# LDO_LM_POWER_two_78.net
KiCad netlist of a schematic drawn in Altium Designer
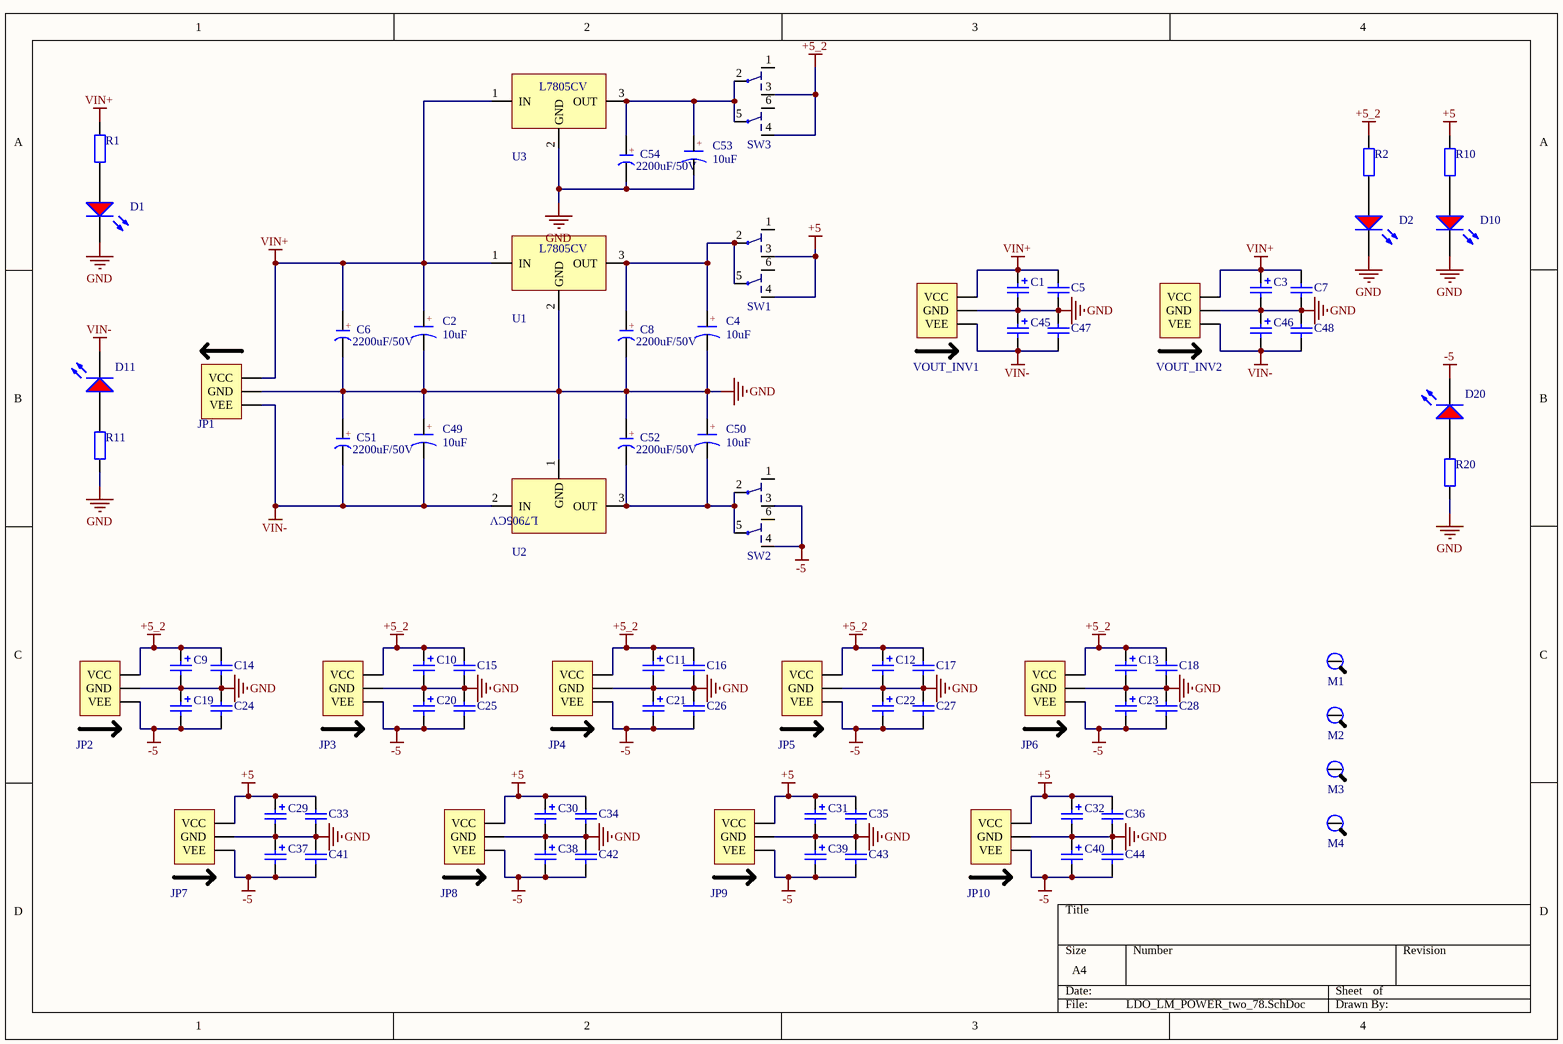
[diagram p0: LDO_LM_POWER_two_78.SchDoc]

(export (version "E")
  (design (tool "Eeschema 10.0.6"))
  (components
    (comp (ref "C1")
      (value "10uF (106) ±10% 16V")
      (footprint "CASE-A_3216")
      (description "钽电容")
      (libsource (lib "JLC") (part "3216 10uF (106) 10% 16V"))
    )
    (comp (ref "C2")
      (value "10uF")
      (footprint "226C")
      (description "贴片钽电容")
      (fields (field (name "Comment") "CAP+"))
      (libsource (lib "Cooperation") (part "0CAP+"))
    )
    (comp (ref "C3")
      (value "10uF (106) ±10% 16V")
      (footprint "CASE-A_3216")
      (description "钽电容")
      (libsource (lib "JLC") (part "3216 10uF (106) 10% 16V"))
    )
    (comp (ref "C4")
      (value "10uF")
      (footprint "226C")
      (description "贴片钽电容")
      (fields (field (name "Comment") "CAP+"))
      (libsource (lib "Cooperation") (part "0CAP+"))
    )
    (comp (ref "C5")
      (value "100nF (104) 10% 50V")
      (footprint "0603_C")
      (description "贴片电容")
      (libsource (lib "JLC") (part "0603 100nF (104) 10% 50V"))
    )
    (comp (ref "C6")
      (value "2200uF/50V")
      (footprint "2200uF/50V")
      (description "直插电解电容")
      (libsource (lib "Cooperation") (part "CAP_2200uF/50V"))
    )
    (comp (ref "C7")
      (value "100nF (104) 10% 50V")
      (footprint "0603_C")
      (description "贴片电容")
      (libsource (lib "JLC") (part "0603 100nF (104) 10% 50V"))
    )
    (comp (ref "C8")
      (value "2200uF/50V")
      (footprint "2200uF/50V")
      (description "直插电解电容")
      (libsource (lib "Cooperation") (part "CAP_2200uF/50V"))
    )
    (comp (ref "C9")
      (value "10uF (106) ±10% 16V")
      (footprint "CASE-A_3216")
      (description "钽电容")
      (libsource (lib "JLC") (part "3216 10uF (106) 10% 16V"))
    )
    (comp (ref "C10")
      (value "10uF (106) ±10% 16V")
      (footprint "CASE-A_3216")
      (description "钽电容")
      (libsource (lib "JLC") (part "3216 10uF (106) 10% 16V"))
    )
    (comp (ref "C11")
      (value "10uF (106) ±10% 16V")
      (footprint "CASE-A_3216")
      (description "钽电容")
      (libsource (lib "JLC") (part "3216 10uF (106) 10% 16V"))
    )
    (comp (ref "C12")
      (value "10uF (106) ±10% 16V")
      (footprint "CASE-A_3216")
      (description "钽电容")
      (libsource (lib "JLC") (part "3216 10uF (106) 10% 16V"))
    )
    (comp (ref "C13")
      (value "10uF (106) ±10% 16V")
      (footprint "CASE-A_3216")
      (description "钽电容")
      (libsource (lib "JLC") (part "3216 10uF (106) 10% 16V"))
    )
    (comp (ref "C14")
      (value "100nF (104) 10% 50V")
      (footprint "0603_C")
      (description "贴片电容")
      (libsource (lib "JLC") (part "0603 100nF (104) 10% 50V"))
    )
    (comp (ref "C15")
      (value "100nF (104) 10% 50V")
      (footprint "0603_C")
      (description "贴片电容")
      (libsource (lib "JLC") (part "0603 100nF (104) 10% 50V"))
    )
    (comp (ref "C16")
      (value "100nF (104) 10% 50V")
      (footprint "0603_C")
      (description "贴片电容")
      (libsource (lib "JLC") (part "0603 100nF (104) 10% 50V"))
    )
    (comp (ref "C17")
      (value "100nF (104) 10% 50V")
      (footprint "0603_C")
      (description "贴片电容")
      (libsource (lib "JLC") (part "0603 100nF (104) 10% 50V"))
    )
    (comp (ref "C18")
      (value "100nF (104) 10% 50V")
      (footprint "0603_C")
      (description "贴片电容")
      (libsource (lib "JLC") (part "0603 100nF (104) 10% 50V"))
    )
    (comp (ref "C19")
      (value "10uF (106) ±10% 16V")
      (footprint "CASE-A_3216")
      (description "钽电容")
      (libsource (lib "JLC") (part "3216 10uF (106) 10% 16V"))
    )
    (comp (ref "C20")
      (value "10uF (106) ±10% 16V")
      (footprint "CASE-A_3216")
      (description "钽电容")
      (libsource (lib "JLC") (part "3216 10uF (106) 10% 16V"))
    )
    (comp (ref "C21")
      (value "10uF (106) ±10% 16V")
      (footprint "CASE-A_3216")
      (description "钽电容")
      (libsource (lib "JLC") (part "3216 10uF (106) 10% 16V"))
    )
    (comp (ref "C22")
      (value "10uF (106) ±10% 16V")
      (footprint "CASE-A_3216")
      (description "钽电容")
      (libsource (lib "JLC") (part "3216 10uF (106) 10% 16V"))
    )
    (comp (ref "C23")
      (value "10uF (106) ±10% 16V")
      (footprint "CASE-A_3216")
      (description "钽电容")
      (libsource (lib "JLC") (part "3216 10uF (106) 10% 16V"))
    )
    (comp (ref "C24")
      (value "100nF (104) 10% 50V")
      (footprint "0603_C")
      (description "贴片电容")
      (libsource (lib "JLC") (part "0603 100nF (104) 10% 50V"))
    )
    (comp (ref "C25")
      (value "100nF (104) 10% 50V")
      (footprint "0603_C")
      (description "贴片电容")
      (libsource (lib "JLC") (part "0603 100nF (104) 10% 50V"))
    )
    (comp (ref "C26")
      (value "100nF (104) 10% 50V")
      (footprint "0603_C")
      (description "贴片电容")
      (libsource (lib "JLC") (part "0603 100nF (104) 10% 50V"))
    )
    (comp (ref "C27")
      (value "100nF (104) 10% 50V")
      (footprint "0603_C")
      (description "贴片电容")
      (libsource (lib "JLC") (part "0603 100nF (104) 10% 50V"))
    )
    (comp (ref "C28")
      (value "100nF (104) 10% 50V")
      (footprint "0603_C")
      (description "贴片电容")
      (libsource (lib "JLC") (part "0603 100nF (104) 10% 50V"))
    )
    (comp (ref "C29")
      (value "10uF (106) ±10% 16V")
      (footprint "CASE-A_3216")
      (description "钽电容")
      (libsource (lib "JLC") (part "3216 10uF (106) 10% 16V"))
    )
    (comp (ref "C30")
      (value "10uF (106) ±10% 16V")
      (footprint "CASE-A_3216")
      (description "钽电容")
      (libsource (lib "JLC") (part "3216 10uF (106) 10% 16V"))
    )
    (comp (ref "C31")
      (value "10uF (106) ±10% 16V")
      (footprint "CASE-A_3216")
      (description "钽电容")
      (libsource (lib "JLC") (part "3216 10uF (106) 10% 16V"))
    )
    (comp (ref "C32")
      (value "10uF (106) ±10% 16V")
      (footprint "CASE-A_3216")
      (description "钽电容")
      (libsource (lib "JLC") (part "3216 10uF (106) 10% 16V"))
    )
    (comp (ref "C33")
      (value "100nF (104) 10% 50V")
      (footprint "0603_C")
      (description "贴片电容")
      (libsource (lib "JLC") (part "0603 100nF (104) 10% 50V"))
    )
    (comp (ref "C34")
      (value "100nF (104) 10% 50V")
      (footprint "0603_C")
      (description "贴片电容")
      (libsource (lib "JLC") (part "0603 100nF (104) 10% 50V"))
    )
    (comp (ref "C35")
      (value "100nF (104) 10% 50V")
      (footprint "0603_C")
      (description "贴片电容")
      (libsource (lib "JLC") (part "0603 100nF (104) 10% 50V"))
    )
    (comp (ref "C36")
      (value "100nF (104) 10% 50V")
      (footprint "0603_C")
      (description "贴片电容")
      (libsource (lib "JLC") (part "0603 100nF (104) 10% 50V"))
    )
    (comp (ref "C37")
      (value "10uF (106) ±10% 16V")
      (footprint "CASE-A_3216")
      (description "钽电容")
      (libsource (lib "JLC") (part "3216 10uF (106) 10% 16V"))
    )
    (comp (ref "C38")
      (value "10uF (106) ±10% 16V")
      (footprint "CASE-A_3216")
      (description "钽电容")
      (libsource (lib "JLC") (part "3216 10uF (106) 10% 16V"))
    )
    (comp (ref "C39")
      (value "10uF (106) ±10% 16V")
      (footprint "CASE-A_3216")
      (description "钽电容")
      (libsource (lib "JLC") (part "3216 10uF (106) 10% 16V"))
    )
    (comp (ref "C40")
      (value "10uF (106) ±10% 16V")
      (footprint "CASE-A_3216")
      (description "钽电容")
      (libsource (lib "JLC") (part "3216 10uF (106) 10% 16V"))
    )
    (comp (ref "C41")
      (value "100nF (104) 10% 50V")
      (footprint "0603_C")
      (description "贴片电容")
      (libsource (lib "JLC") (part "0603 100nF (104) 10% 50V"))
    )
    (comp (ref "C42")
      (value "100nF (104) 10% 50V")
      (footprint "0603_C")
      (description "贴片电容")
      (libsource (lib "JLC") (part "0603 100nF (104) 10% 50V"))
    )
    (comp (ref "C43")
      (value "100nF (104) 10% 50V")
      (footprint "0603_C")
      (description "贴片电容")
      (libsource (lib "JLC") (part "0603 100nF (104) 10% 50V"))
    )
    (comp (ref "C44")
      (value "100nF (104) 10% 50V")
      (footprint "0603_C")
      (description "贴片电容")
      (libsource (lib "JLC") (part "0603 100nF (104) 10% 50V"))
    )
    (comp (ref "C45")
      (value "10uF (106) ±10% 16V")
      (footprint "CASE-A_3216")
      (description "钽电容")
      (libsource (lib "JLC") (part "3216 10uF (106) 10% 16V"))
    )
    (comp (ref "C46")
      (value "10uF (106) ±10% 16V")
      (footprint "CASE-A_3216")
      (description "钽电容")
      (libsource (lib "JLC") (part "3216 10uF (106) 10% 16V"))
    )
    (comp (ref "C47")
      (value "100nF (104) 10% 50V")
      (footprint "0603_C")
      (description "贴片电容")
      (libsource (lib "JLC") (part "0603 100nF (104) 10% 50V"))
    )
    (comp (ref "C48")
      (value "100nF (104) 10% 50V")
      (footprint "0603_C")
      (description "贴片电容")
      (libsource (lib "JLC") (part "0603 100nF (104) 10% 50V"))
    )
    (comp (ref "C49")
      (value "10uF")
      (footprint "226C")
      (description "贴片钽电容")
      (fields (field (name "Comment") "CAP+"))
      (libsource (lib "Cooperation") (part "0CAP+"))
    )
    (comp (ref "C50")
      (value "10uF")
      (footprint "226C")
      (description "贴片钽电容")
      (fields (field (name "Comment") "CAP+"))
      (libsource (lib "Cooperation") (part "0CAP+"))
    )
    (comp (ref "C51")
      (value "2200uF/50V")
      (footprint "2200uF/50V")
      (description "直插电解电容")
      (libsource (lib "Cooperation") (part "CAP_2200uF/50V"))
    )
    (comp (ref "C52")
      (value "2200uF/50V")
      (footprint "2200uF/50V")
      (description "直插电解电容")
      (libsource (lib "Cooperation") (part "CAP_2200uF/50V"))
    )
    (comp (ref "C53")
      (value "10uF")
      (footprint "226C")
      (description "贴片钽电容")
      (fields (field (name "Comment") "CAP+"))
      (libsource (lib "Cooperation") (part "0CAP+"))
    )
    (comp (ref "C54")
      (value "2200uF/50V")
      (footprint "2200uF/50V")
      (description "直插电解电容")
      (libsource (lib "Cooperation") (part "CAP_2200uF/50V"))
    )
    (comp (ref "D1")
      (value "红灯 0603")
      (footprint "0603_LED_S1")
      (description "发光二极管")
      (libsource (lib "JLC") (part "0603 红灯"))
    )
    (comp (ref "D2")
      (value "红灯 0603")
      (footprint "0603_LED_S1")
      (description "发光二极管")
      (libsource (lib "JLC") (part "0603 红灯"))
    )
    (comp (ref "D10")
      (value "红灯 0603")
      (footprint "0603_LED_S1")
      (description "发光二极管")
      (libsource (lib "JLC") (part "0603 红灯"))
    )
    (comp (ref "D11")
      (value "红灯 0603")
      (footprint "0603_LED_S1")
      (description "发光二极管")
      (libsource (lib "JLC") (part "0603 红灯"))
    )
    (comp (ref "D20")
      (value "红灯 0603")
      (footprint "0603_LED_S1")
      (description "发光二极管")
      (libsource (lib "JLC") (part "0603 红灯"))
    )
    (comp (ref "JP1")
      (value "HDR-1X3")
      (footprint "Power_IN_3.81-3P")
      (description "3P接插件,模块双电源供电口")
      (fields (field (name "版权归属") "源创客"))
      (libsource (lib "Cooperation") (part "PORT_Power_IN3"))
    )
    (comp (ref "JP2")
      (value "HDR-1X3")
      (footprint "Power_OUT_3.81-3P")
      (description "3P接插件,双电源供电口")
      (fields (field (name "版权归属") "源创客"))
      (libsource (lib "Cooperation") (part "PORT_Power_OUT3"))
    )
    (comp (ref "JP3")
      (value "HDR-1X3")
      (footprint "Power_OUT_3.81-3P")
      (description "3P接插件,双电源供电口")
      (fields (field (name "版权归属") "源创客"))
      (libsource (lib "Cooperation") (part "PORT_Power_OUT3"))
    )
    (comp (ref "JP4")
      (value "HDR-1X3")
      (footprint "Power_OUT_3.81-3P")
      (description "3P接插件,双电源供电口")
      (fields (field (name "版权归属") "源创客"))
      (libsource (lib "Cooperation") (part "PORT_Power_OUT3"))
    )
    (comp (ref "JP5")
      (value "HDR-1X3")
      (footprint "Power_OUT_3.81-3P")
      (description "3P接插件,双电源供电口")
      (fields (field (name "版权归属") "源创客"))
      (libsource (lib "Cooperation") (part "PORT_Power_OUT3"))
    )
    (comp (ref "JP6")
      (value "HDR-1X3")
      (footprint "Power_OUT_3.81-3P")
      (description "3P接插件,双电源供电口")
      (fields (field (name "版权归属") "源创客"))
      (libsource (lib "Cooperation") (part "PORT_Power_OUT3"))
    )
    (comp (ref "JP7")
      (value "HDR-1X3")
      (footprint "Power_OUT_3.81-3P")
      (description "3P接插件,双电源供电口")
      (fields (field (name "版权归属") "源创客"))
      (libsource (lib "Cooperation") (part "PORT_Power_OUT3"))
    )
    (comp (ref "JP8")
      (value "HDR-1X3")
      (footprint "Power_OUT_3.81-3P")
      (description "3P接插件,双电源供电口")
      (fields (field (name "版权归属") "源创客"))
      (libsource (lib "Cooperation") (part "PORT_Power_OUT3"))
    )
    (comp (ref "JP9")
      (value "HDR-1X3")
      (footprint "Power_OUT_3.81-3P")
      (description "3P接插件,双电源供电口")
      (fields (field (name "版权归属") "源创客"))
      (libsource (lib "Cooperation") (part "PORT_Power_OUT3"))
    )
    (comp (ref "JP10")
      (value "HDR-1X3")
      (footprint "Power_OUT_3.81-3P")
      (description "3P接插件,双电源供电口")
      (fields (field (name "版权归属") "源创客"))
      (libsource (lib "Cooperation") (part "PORT_Power_OUT3"))
    )
    (comp (ref "M1")
      (value "M3")
      (footprint "M3x10_L")
      (description "螺丝")
      (libsource (lib "Cooperation") (part "ELSE_M3_screw"))
    )
    (comp (ref "M2")
      (value "M3")
      (footprint "M3x10_L")
      (description "螺丝")
      (libsource (lib "Cooperation") (part "ELSE_M3_screw"))
    )
    (comp (ref "M3")
      (value "M3")
      (footprint "M3x10_L")
      (description "螺丝")
      (libsource (lib "Cooperation") (part "ELSE_M3_screw"))
    )
    (comp (ref "M4")
      (value "M3")
      (footprint "M3x10_L")
      (description "螺丝")
      (libsource (lib "Cooperation") (part "ELSE_M3_screw"))
    )
    (comp (ref "R1")
      (value "10KΩ (1002) ±1%")
      (footprint "0603_R")
      (description "贴片电阻")
      (libsource (lib "JLC") (part "0603 10KΩ (1002) 1%"))
    )
    (comp (ref "R2")
      (value "10KΩ (1002) ±1%")
      (footprint "0603_R")
      (description "贴片电阻")
      (libsource (lib "JLC") (part "0603 10KΩ (1002) 1%"))
    )
    (comp (ref "R10")
      (value "10KΩ (1002) ±1%")
      (footprint "0603_R")
      (description "贴片电阻")
      (libsource (lib "JLC") (part "0603 10KΩ (1002) 1%"))
    )
    (comp (ref "R11")
      (value "10KΩ (1002) ±1%")
      (footprint "0603_R")
      (description "贴片电阻")
      (libsource (lib "JLC") (part "0603 10KΩ (1002) 1%"))
    )
    (comp (ref "R20")
      (value "10KΩ (1002) ±1%")
      (footprint "0603_R")
      (description "贴片电阻")
      (libsource (lib "JLC") (part "0603 10KΩ (1002) 1%"))
    )
    (comp (ref "SW1")
      (value "SWITCH")
      (footprint "六脚自锁开关")
      (libsource (lib "Cooperation") (part "SWITCH_六脚自锁开关"))
    )
    (comp (ref "SW2")
      (value "SWITCH")
      (footprint "六脚自锁开关")
      (libsource (lib "Cooperation") (part "SWITCH_六脚自锁开关"))
    )
    (comp (ref "SW3")
      (value "SWITCH")
      (footprint "六脚自锁开关")
      (libsource (lib "Cooperation") (part "SWITCH_六脚自锁开关"))
    )
    (comp (ref "U1")
      (value "7805")
      (footprint "TO-220")
      (description "3端稳压")
      (libsource (lib "Cooperation") (part "IC_7805"))
    )
    (comp (ref "U2")
      (value "7905")
      (footprint "TO-220")
      (description "3端稳压")
      (libsource (lib "Cooperation") (part "IC_7905"))
    )
    (comp (ref "U3")
      (value "7805")
      (footprint "TO-220")
      (description "3端稳压")
      (libsource (lib "Cooperation") (part "IC_7805"))
    )
    (comp (ref "VOUT_INV1")
      (value "HDR-1X3")
      (footprint "Power_OUT_3.81-3P")
      (description "3P接插件,双电源供电口")
      (fields (field (name "版权归属") "源创客"))
      (libsource (lib "Cooperation") (part "PORT_Power_OUT3"))
    )
    (comp (ref "VOUT_INV2")
      (value "HDR-1X3")
      (footprint "Power_OUT_3.81-3P")
      (description "3P接插件,双电源供电口")
      (fields (field (name "版权归属") "源创客"))
      (libsource (lib "Cooperation") (part "PORT_Power_OUT3"))
    )
  )
  (nets
    (net (code "1") (name "+5") (class "Default")
      (node (ref "C29") (pin "1") (pinfunction "1_1") (pintype "passive"))
      (node (ref "C30") (pin "1") (pinfunction "1_1") (pintype "passive"))
      (node (ref "C31") (pin "1") (pinfunction "1_1") (pintype "passive"))
      (node (ref "C32") (pin "1") (pinfunction "1_1") (pintype "passive"))
      (node (ref "C33") (pin "2") (pinfunction "2_2") (pintype "passive"))
      (node (ref "C34") (pin "2") (pinfunction "2_2") (pintype "passive"))
      (node (ref "C35") (pin "2") (pinfunction "2_2") (pintype "passive"))
      (node (ref "C36") (pin "2") (pinfunction "2_2") (pintype "passive"))
      (node (ref "JP10") (pin "3") (pinfunction "VCC_3") (pintype "passive"))
      (node (ref "JP7") (pin "3") (pinfunction "VCC_3") (pintype "passive"))
      (node (ref "JP8") (pin "3") (pinfunction "VCC_3") (pintype "passive"))
      (node (ref "JP9") (pin "3") (pinfunction "VCC_3") (pintype "passive"))
      (node (ref "R10") (pin "2") (pinfunction "2_2") (pintype "passive"))
      (node (ref "SW1") (pin "3") (pinfunction "3_3") (pintype "passive"))
      (node (ref "SW1") (pin "4") (pinfunction "4_4") (pintype "passive"))
    )
    (net (code "2") (name "+5_2") (class "Default")
      (node (ref "C10") (pin "1") (pinfunction "1_1") (pintype "passive"))
      (node (ref "C11") (pin "1") (pinfunction "1_1") (pintype "passive"))
      (node (ref "C12") (pin "1") (pinfunction "1_1") (pintype "passive"))
      (node (ref "C13") (pin "1") (pinfunction "1_1") (pintype "passive"))
      (node (ref "C14") (pin "2") (pinfunction "2_2") (pintype "passive"))
      (node (ref "C15") (pin "2") (pinfunction "2_2") (pintype "passive"))
      (node (ref "C16") (pin "2") (pinfunction "2_2") (pintype "passive"))
      (node (ref "C17") (pin "2") (pinfunction "2_2") (pintype "passive"))
      (node (ref "C18") (pin "2") (pinfunction "2_2") (pintype "passive"))
      (node (ref "C9") (pin "1") (pinfunction "1_1") (pintype "passive"))
      (node (ref "JP2") (pin "3") (pinfunction "VCC_3") (pintype "passive"))
      (node (ref "JP3") (pin "3") (pinfunction "VCC_3") (pintype "passive"))
      (node (ref "JP4") (pin "3") (pinfunction "VCC_3") (pintype "passive"))
      (node (ref "JP5") (pin "3") (pinfunction "VCC_3") (pintype "passive"))
      (node (ref "JP6") (pin "3") (pinfunction "VCC_3") (pintype "passive"))
      (node (ref "R2") (pin "2") (pinfunction "2_2") (pintype "passive"))
      (node (ref "SW3") (pin "3") (pinfunction "3_3") (pintype "passive"))
      (node (ref "SW3") (pin "4") (pinfunction "4_4") (pintype "passive"))
    )
    (net (code "3") (name "-5") (class "Default")
      (node (ref "C19") (pin "2") (pinfunction "2_2") (pintype "passive"))
      (node (ref "C20") (pin "2") (pinfunction "2_2") (pintype "passive"))
      (node (ref "C21") (pin "2") (pinfunction "2_2") (pintype "passive"))
      (node (ref "C22") (pin "2") (pinfunction "2_2") (pintype "passive"))
      (node (ref "C23") (pin "2") (pinfunction "2_2") (pintype "passive"))
      (node (ref "C24") (pin "1") (pinfunction "1_1") (pintype "passive"))
      (node (ref "C25") (pin "1") (pinfunction "1_1") (pintype "passive"))
      (node (ref "C26") (pin "1") (pinfunction "1_1") (pintype "passive"))
      (node (ref "C27") (pin "1") (pinfunction "1_1") (pintype "passive"))
      (node (ref "C28") (pin "1") (pinfunction "1_1") (pintype "passive"))
      (node (ref "C37") (pin "2") (pinfunction "2_2") (pintype "passive"))
      (node (ref "C38") (pin "2") (pinfunction "2_2") (pintype "passive"))
      (node (ref "C39") (pin "2") (pinfunction "2_2") (pintype "passive"))
      (node (ref "C40") (pin "2") (pinfunction "2_2") (pintype "passive"))
      (node (ref "C41") (pin "1") (pinfunction "1_1") (pintype "passive"))
      (node (ref "C42") (pin "1") (pinfunction "1_1") (pintype "passive"))
      (node (ref "C43") (pin "1") (pinfunction "1_1") (pintype "passive"))
      (node (ref "C44") (pin "1") (pinfunction "1_1") (pintype "passive"))
      (node (ref "D20") (pin "K") (pinfunction "K_K") (pintype "passive"))
      (node (ref "JP10") (pin "1") (pinfunction "VEE_1") (pintype "passive"))
      (node (ref "JP2") (pin "1") (pinfunction "VEE_1") (pintype "passive"))
      (node (ref "JP3") (pin "1") (pinfunction "VEE_1") (pintype "passive"))
      (node (ref "JP4") (pin "1") (pinfunction "VEE_1") (pintype "passive"))
      (node (ref "JP5") (pin "1") (pinfunction "VEE_1") (pintype "passive"))
      (node (ref "JP6") (pin "1") (pinfunction "VEE_1") (pintype "passive"))
      (node (ref "JP7") (pin "1") (pinfunction "VEE_1") (pintype "passive"))
      (node (ref "JP8") (pin "1") (pinfunction "VEE_1") (pintype "passive"))
      (node (ref "JP9") (pin "1") (pinfunction "VEE_1") (pintype "passive"))
      (node (ref "SW2") (pin "3") (pinfunction "3_3") (pintype "passive"))
      (node (ref "SW2") (pin "4") (pinfunction "4_4") (pintype "passive"))
    )
    (net (code "4") (name "GND") (class "Default")
      (node (ref "C1") (pin "2") (pinfunction "2_2") (pintype "passive"))
      (node (ref "C10") (pin "2") (pinfunction "2_2") (pintype "passive"))
      (node (ref "C11") (pin "2") (pinfunction "2_2") (pintype "passive"))
      (node (ref "C12") (pin "2") (pinfunction "2_2") (pintype "passive"))
      (node (ref "C13") (pin "2") (pinfunction "2_2") (pintype "passive"))
      (node (ref "C14") (pin "1") (pinfunction "1_1") (pintype "passive"))
      (node (ref "C15") (pin "1") (pinfunction "1_1") (pintype "passive"))
      (node (ref "C16") (pin "1") (pinfunction "1_1") (pintype "passive"))
      (node (ref "C17") (pin "1") (pinfunction "1_1") (pintype "passive"))
      (node (ref "C18") (pin "1") (pinfunction "1_1") (pintype "passive"))
      (node (ref "C19") (pin "1") (pinfunction "1_1") (pintype "passive"))
      (node (ref "C2") (pin "2") (pinfunction "K_2") (pintype "passive"))
      (node (ref "C20") (pin "1") (pinfunction "1_1") (pintype "passive"))
      (node (ref "C21") (pin "1") (pinfunction "1_1") (pintype "passive"))
      (node (ref "C22") (pin "1") (pinfunction "1_1") (pintype "passive"))
      (node (ref "C23") (pin "1") (pinfunction "1_1") (pintype "passive"))
      (node (ref "C24") (pin "2") (pinfunction "2_2") (pintype "passive"))
      (node (ref "C25") (pin "2") (pinfunction "2_2") (pintype "passive"))
      (node (ref "C26") (pin "2") (pinfunction "2_2") (pintype "passive"))
      (node (ref "C27") (pin "2") (pinfunction "2_2") (pintype "passive"))
      (node (ref "C28") (pin "2") (pinfunction "2_2") (pintype "passive"))
      (node (ref "C29") (pin "2") (pinfunction "2_2") (pintype "passive"))
      (node (ref "C3") (pin "2") (pinfunction "2_2") (pintype "passive"))
      (node (ref "C30") (pin "2") (pinfunction "2_2") (pintype "passive"))
      (node (ref "C31") (pin "2") (pinfunction "2_2") (pintype "passive"))
      (node (ref "C32") (pin "2") (pinfunction "2_2") (pintype "passive"))
      (node (ref "C33") (pin "1") (pinfunction "1_1") (pintype "passive"))
      (node (ref "C34") (pin "1") (pinfunction "1_1") (pintype "passive"))
      (node (ref "C35") (pin "1") (pinfunction "1_1") (pintype "passive"))
      (node (ref "C36") (pin "1") (pinfunction "1_1") (pintype "passive"))
      (node (ref "C37") (pin "1") (pinfunction "1_1") (pintype "passive"))
      (node (ref "C38") (pin "1") (pinfunction "1_1") (pintype "passive"))
      (node (ref "C39") (pin "1") (pinfunction "1_1") (pintype "passive"))
      (node (ref "C4") (pin "2") (pinfunction "K_2") (pintype "passive"))
      (node (ref "C40") (pin "1") (pinfunction "1_1") (pintype "passive"))
      (node (ref "C41") (pin "2") (pinfunction "2_2") (pintype "passive"))
      (node (ref "C42") (pin "2") (pinfunction "2_2") (pintype "passive"))
      (node (ref "C43") (pin "2") (pinfunction "2_2") (pintype "passive"))
      (node (ref "C44") (pin "2") (pinfunction "2_2") (pintype "passive"))
      (node (ref "C45") (pin "1") (pinfunction "1_1") (pintype "passive"))
      (node (ref "C46") (pin "1") (pinfunction "1_1") (pintype "passive"))
      (node (ref "C47") (pin "2") (pinfunction "2_2") (pintype "passive"))
      (node (ref "C48") (pin "2") (pinfunction "2_2") (pintype "passive"))
      (node (ref "C49") (pin "1") (pinfunction "A_1") (pintype "passive"))
      (node (ref "C5") (pin "1") (pinfunction "1_1") (pintype "passive"))
      (node (ref "C50") (pin "1") (pinfunction "A_1") (pintype "passive"))
      (node (ref "C51") (pin "1") (pinfunction "A_1") (pintype "passive"))
      (node (ref "C52") (pin "1") (pinfunction "A_1") (pintype "passive"))
      (node (ref "C53") (pin "2") (pinfunction "K_2") (pintype "passive"))
      (node (ref "C54") (pin "2") (pinfunction "K_2") (pintype "passive"))
      (node (ref "C6") (pin "2") (pinfunction "K_2") (pintype "passive"))
      (node (ref "C7") (pin "1") (pinfunction "1_1") (pintype "passive"))
      (node (ref "C8") (pin "2") (pinfunction "K_2") (pintype "passive"))
      (node (ref "C9") (pin "2") (pinfunction "2_2") (pintype "passive"))
      (node (ref "D1") (pin "K") (pinfunction "K_K") (pintype "passive"))
      (node (ref "D10") (pin "K") (pinfunction "K_K") (pintype "passive"))
      (node (ref "D2") (pin "K") (pinfunction "K_K") (pintype "passive"))
      (node (ref "JP1") (pin "2") (pinfunction "GND_2") (pintype "passive"))
      (node (ref "JP10") (pin "2") (pinfunction "GND_2") (pintype "passive"))
      (node (ref "JP2") (pin "2") (pinfunction "GND_2") (pintype "passive"))
      (node (ref "JP3") (pin "2") (pinfunction "GND_2") (pintype "passive"))
      (node (ref "JP4") (pin "2") (pinfunction "GND_2") (pintype "passive"))
      (node (ref "JP5") (pin "2") (pinfunction "GND_2") (pintype "passive"))
      (node (ref "JP6") (pin "2") (pinfunction "GND_2") (pintype "passive"))
      (node (ref "JP7") (pin "2") (pinfunction "GND_2") (pintype "passive"))
      (node (ref "JP8") (pin "2") (pinfunction "GND_2") (pintype "passive"))
      (node (ref "JP9") (pin "2") (pinfunction "GND_2") (pintype "passive"))
      (node (ref "R11") (pin "1") (pinfunction "1_1") (pintype "passive"))
      (node (ref "R20") (pin "1") (pinfunction "1_1") (pintype "passive"))
      (node (ref "U1") (pin "2") (pinfunction "GND_2") (pintype "passive"))
      (node (ref "U2") (pin "1") (pinfunction "GND_1") (pintype "passive"))
      (node (ref "U3") (pin "2") (pinfunction "GND_2") (pintype "passive"))
      (node (ref "VOUT_INV1") (pin "2") (pinfunction "GND_2") (pintype "passive"))
      (node (ref "VOUT_INV2") (pin "2") (pinfunction "GND_2") (pintype "passive"))
    )
    (net (code "5") (name "Net-(C4-A)") (class "Default")
      (node (ref "C4") (pin "1") (pinfunction "A_1") (pintype "passive"))
      (node (ref "C8") (pin "1") (pinfunction "A_1") (pintype "passive"))
      (node (ref "SW1") (pin "2") (pinfunction "2_2") (pintype "passive"))
      (node (ref "SW1") (pin "5") (pinfunction "5_5") (pintype "passive"))
      (node (ref "U1") (pin "3") (pinfunction "OUT_3") (pintype "passive"))
    )
    (net (code "6") (name "Net-(C50-K)") (class "Default")
      (node (ref "C50") (pin "2") (pinfunction "K_2") (pintype "passive"))
      (node (ref "C52") (pin "2") (pinfunction "K_2") (pintype "passive"))
      (node (ref "SW2") (pin "2") (pinfunction "2_2") (pintype "passive"))
      (node (ref "SW2") (pin "5") (pinfunction "5_5") (pintype "passive"))
      (node (ref "U2") (pin "3") (pinfunction "OUT_3") (pintype "passive"))
    )
    (net (code "7") (name "Net-(C53-A)") (class "Default")
      (node (ref "C53") (pin "1") (pinfunction "A_1") (pintype "passive"))
      (node (ref "C54") (pin "1") (pinfunction "A_1") (pintype "passive"))
      (node (ref "SW3") (pin "2") (pinfunction "2_2") (pintype "passive"))
      (node (ref "SW3") (pin "5") (pinfunction "5_5") (pintype "passive"))
      (node (ref "U3") (pin "3") (pinfunction "OUT_3") (pintype "passive"))
    )
    (net (code "8") (name "Net-(D1-PadA)") (class "Default")
      (node (ref "D1") (pin "A") (pinfunction "A_A") (pintype "passive"))
      (node (ref "R1") (pin "1") (pinfunction "1_1") (pintype "passive"))
    )
    (net (code "9") (name "Net-(D2-PadA)") (class "Default")
      (node (ref "D2") (pin "A") (pinfunction "A_A") (pintype "passive"))
      (node (ref "R2") (pin "1") (pinfunction "1_1") (pintype "passive"))
    )
    (net (code "10") (name "Net-(D10-PadA)") (class "Default")
      (node (ref "D10") (pin "A") (pinfunction "A_A") (pintype "passive"))
      (node (ref "R10") (pin "1") (pinfunction "1_1") (pintype "passive"))
    )
    (net (code "11") (name "Net-(D11-PadA)") (class "Default")
      (node (ref "D11") (pin "A") (pinfunction "A_A") (pintype "passive"))
      (node (ref "R11") (pin "2") (pinfunction "2_2") (pintype "passive"))
    )
    (net (code "12") (name "Net-(D20-PadA)") (class "Default")
      (node (ref "D20") (pin "A") (pinfunction "A_A") (pintype "passive"))
      (node (ref "R20") (pin "2") (pinfunction "2_2") (pintype "passive"))
    )
    (net (code "13") (name "VIN+") (class "Default")
      (node (ref "C1") (pin "1") (pinfunction "1_1") (pintype "passive"))
      (node (ref "C2") (pin "1") (pinfunction "A_1") (pintype "passive"))
      (node (ref "C3") (pin "1") (pinfunction "1_1") (pintype "passive"))
      (node (ref "C5") (pin "2") (pinfunction "2_2") (pintype "passive"))
      (node (ref "C6") (pin "1") (pinfunction "A_1") (pintype "passive"))
      (node (ref "C7") (pin "2") (pinfunction "2_2") (pintype "passive"))
      (node (ref "JP1") (pin "1") (pinfunction "VCC_1") (pintype "passive"))
      (node (ref "R1") (pin "2") (pinfunction "2_2") (pintype "passive"))
      (node (ref "U1") (pin "1") (pinfunction "IN_1") (pintype "passive"))
      (node (ref "U3") (pin "1") (pinfunction "IN_1") (pintype "passive"))
      (node (ref "VOUT_INV1") (pin "3") (pinfunction "VCC_3") (pintype "passive"))
      (node (ref "VOUT_INV2") (pin "3") (pinfunction "VCC_3") (pintype "passive"))
    )
    (net (code "14") (name "VIN-") (class "Default")
      (node (ref "C45") (pin "2") (pinfunction "2_2") (pintype "passive"))
      (node (ref "C46") (pin "2") (pinfunction "2_2") (pintype "passive"))
      (node (ref "C47") (pin "1") (pinfunction "1_1") (pintype "passive"))
      (node (ref "C48") (pin "1") (pinfunction "1_1") (pintype "passive"))
      (node (ref "C49") (pin "2") (pinfunction "K_2") (pintype "passive"))
      (node (ref "C51") (pin "2") (pinfunction "K_2") (pintype "passive"))
      (node (ref "D11") (pin "K") (pinfunction "K_K") (pintype "passive"))
      (node (ref "JP1") (pin "3") (pinfunction "VEE_3") (pintype "passive"))
      (node (ref "U2") (pin "2") (pinfunction "IN_2") (pintype "passive"))
      (node (ref "VOUT_INV1") (pin "1") (pinfunction "VEE_1") (pintype "passive"))
      (node (ref "VOUT_INV2") (pin "1") (pinfunction "VEE_1") (pintype "passive"))
    )
    (net (code "15") (name "unconnected-(M1-Pad1)") (class "Default")
      (node (ref "M1") (pin "1") (pinfunction "1_1") (pintype "passive"))
    )
    (net (code "16") (name "unconnected-(M2-Pad1)") (class "Default")
      (node (ref "M2") (pin "1") (pinfunction "1_1") (pintype "passive"))
    )
    (net (code "17") (name "unconnected-(M3-Pad1)") (class "Default")
      (node (ref "M3") (pin "1") (pinfunction "1_1") (pintype "passive"))
    )
    (net (code "18") (name "unconnected-(M4-Pad1)") (class "Default")
      (node (ref "M4") (pin "1") (pinfunction "1_1") (pintype "passive"))
    )
    (net (code "19") (name "unconnected-(SW1-Pad1)") (class "Default")
      (node (ref "SW1") (pin "1") (pinfunction "1_1") (pintype "passive"))
    )
    (net (code "20") (name "unconnected-(SW1-Pad6)") (class "Default")
      (node (ref "SW1") (pin "6") (pinfunction "6_6") (pintype "passive"))
    )
    (net (code "21") (name "unconnected-(SW2-Pad1)") (class "Default")
      (node (ref "SW2") (pin "1") (pinfunction "1_1") (pintype "passive"))
    )
    (net (code "22") (name "unconnected-(SW2-Pad6)") (class "Default")
      (node (ref "SW2") (pin "6") (pinfunction "6_6") (pintype "passive"))
    )
    (net (code "23") (name "unconnected-(SW3-Pad1)") (class "Default")
      (node (ref "SW3") (pin "1") (pinfunction "1_1") (pintype "passive"))
    )
    (net (code "24") (name "unconnected-(SW3-Pad6)") (class "Default")
      (node (ref "SW3") (pin "6") (pinfunction "6_6") (pintype "passive"))
    )
  )
)
